# Viper0_4_1_tmd_probe_6-12.net
KiCad netlist of a schematic drawn in EAGLE
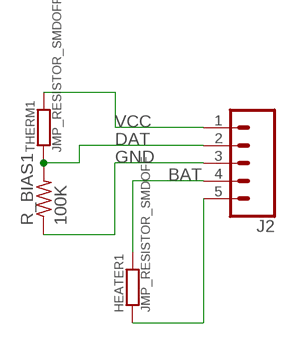
[diagram p0: schematic, sheet 1]

(export (version "E")
  (design (tool "Eeschema 10.0.6"))
  (components
    (comp (ref "HEATER1")
      (value "JMP_RESISTOR_SMDOFF")
      (footprint "eagle-import:JMP_OFF_SMD")
      (libsource (lib "eagle-import") (part "JMP_RESISTOR_SMDOFF"))
    )
    (comp (ref "J2")
      (value "CONN_05NO_SILK")
      (footprint "eagle-import:1X05_NO_SILK")
      (libsource (lib "eagle-import") (part "CONN_05NO_SILK"))
    )
    (comp (ref "R_BIAS1")
      (value "100K")
      (footprint "eagle-import:0805-THM")
      (libsource (lib "eagle-import") (part "FLIPFLOP-RES"))
    )
    (comp (ref "THERM1")
      (value "JMP_RESISTOR_SMDOFF")
      (footprint "eagle-import:JMP_OFF_SMD")
      (libsource (lib "eagle-import") (part "JMP_RESISTOR_SMDOFF"))
    )
  )
  (nets
    (net (code "1") (name "/BAT") (class "Default")
      (node (ref "HEATER1") (pin "2") (pinfunction "P$2_2") (pintype "bidirectional"))
      (node (ref "J2") (pin "4") (pinfunction "4_4") (pintype "passive"))
    )
    (net (code "2") (name "/DAT") (class "Default")
      (node (ref "J2") (pin "2") (pinfunction "2_2") (pintype "passive"))
      (node (ref "R_BIAS1") (pin "2") (pinfunction "2_2") (pintype "passive"))
      (node (ref "THERM1") (pin "1") (pinfunction "P$1_1") (pintype "bidirectional"))
    )
    (net (code "3") (name "/GND") (class "Default")
      (node (ref "HEATER1") (pin "1") (pinfunction "P$1_1") (pintype "bidirectional"))
      (node (ref "J2") (pin "3") (pinfunction "3_3") (pintype "passive"))
      (node (ref "J2") (pin "5") (pinfunction "5_5") (pintype "passive"))
      (node (ref "R_BIAS1") (pin "1") (pinfunction "1_1") (pintype "passive"))
    )
    (net (code "4") (name "/VCC") (class "Default")
      (node (ref "J2") (pin "1") (pinfunction "1_1") (pintype "passive"))
      (node (ref "THERM1") (pin "2") (pinfunction "P$2_2") (pintype "bidirectional"))
    )
  )
)
